# embedded-gw.net
KiCad netlist of a schematic drawn in EAGLE
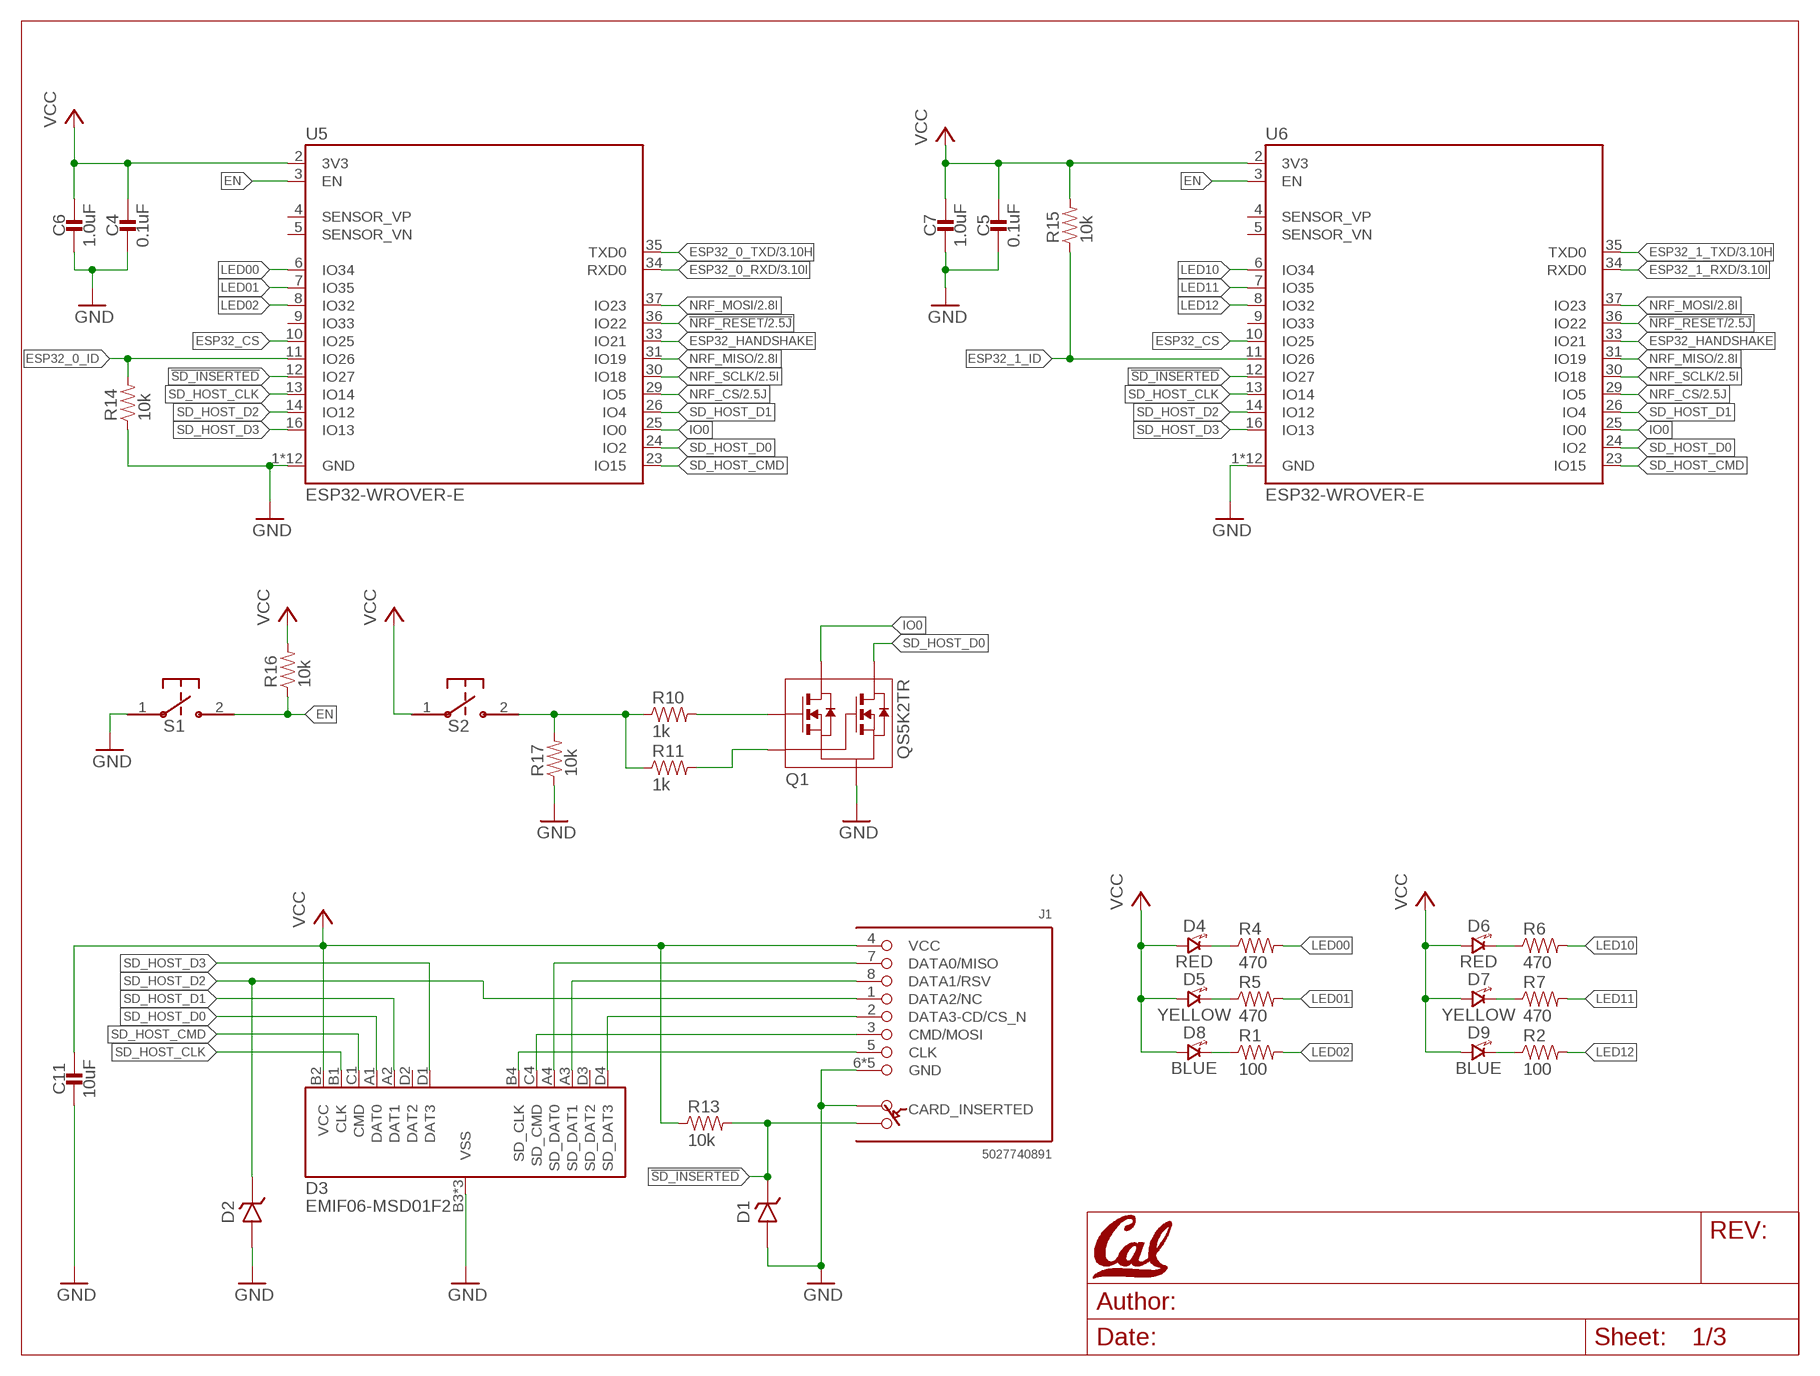
[diagram p0: schematic, sheet 1]
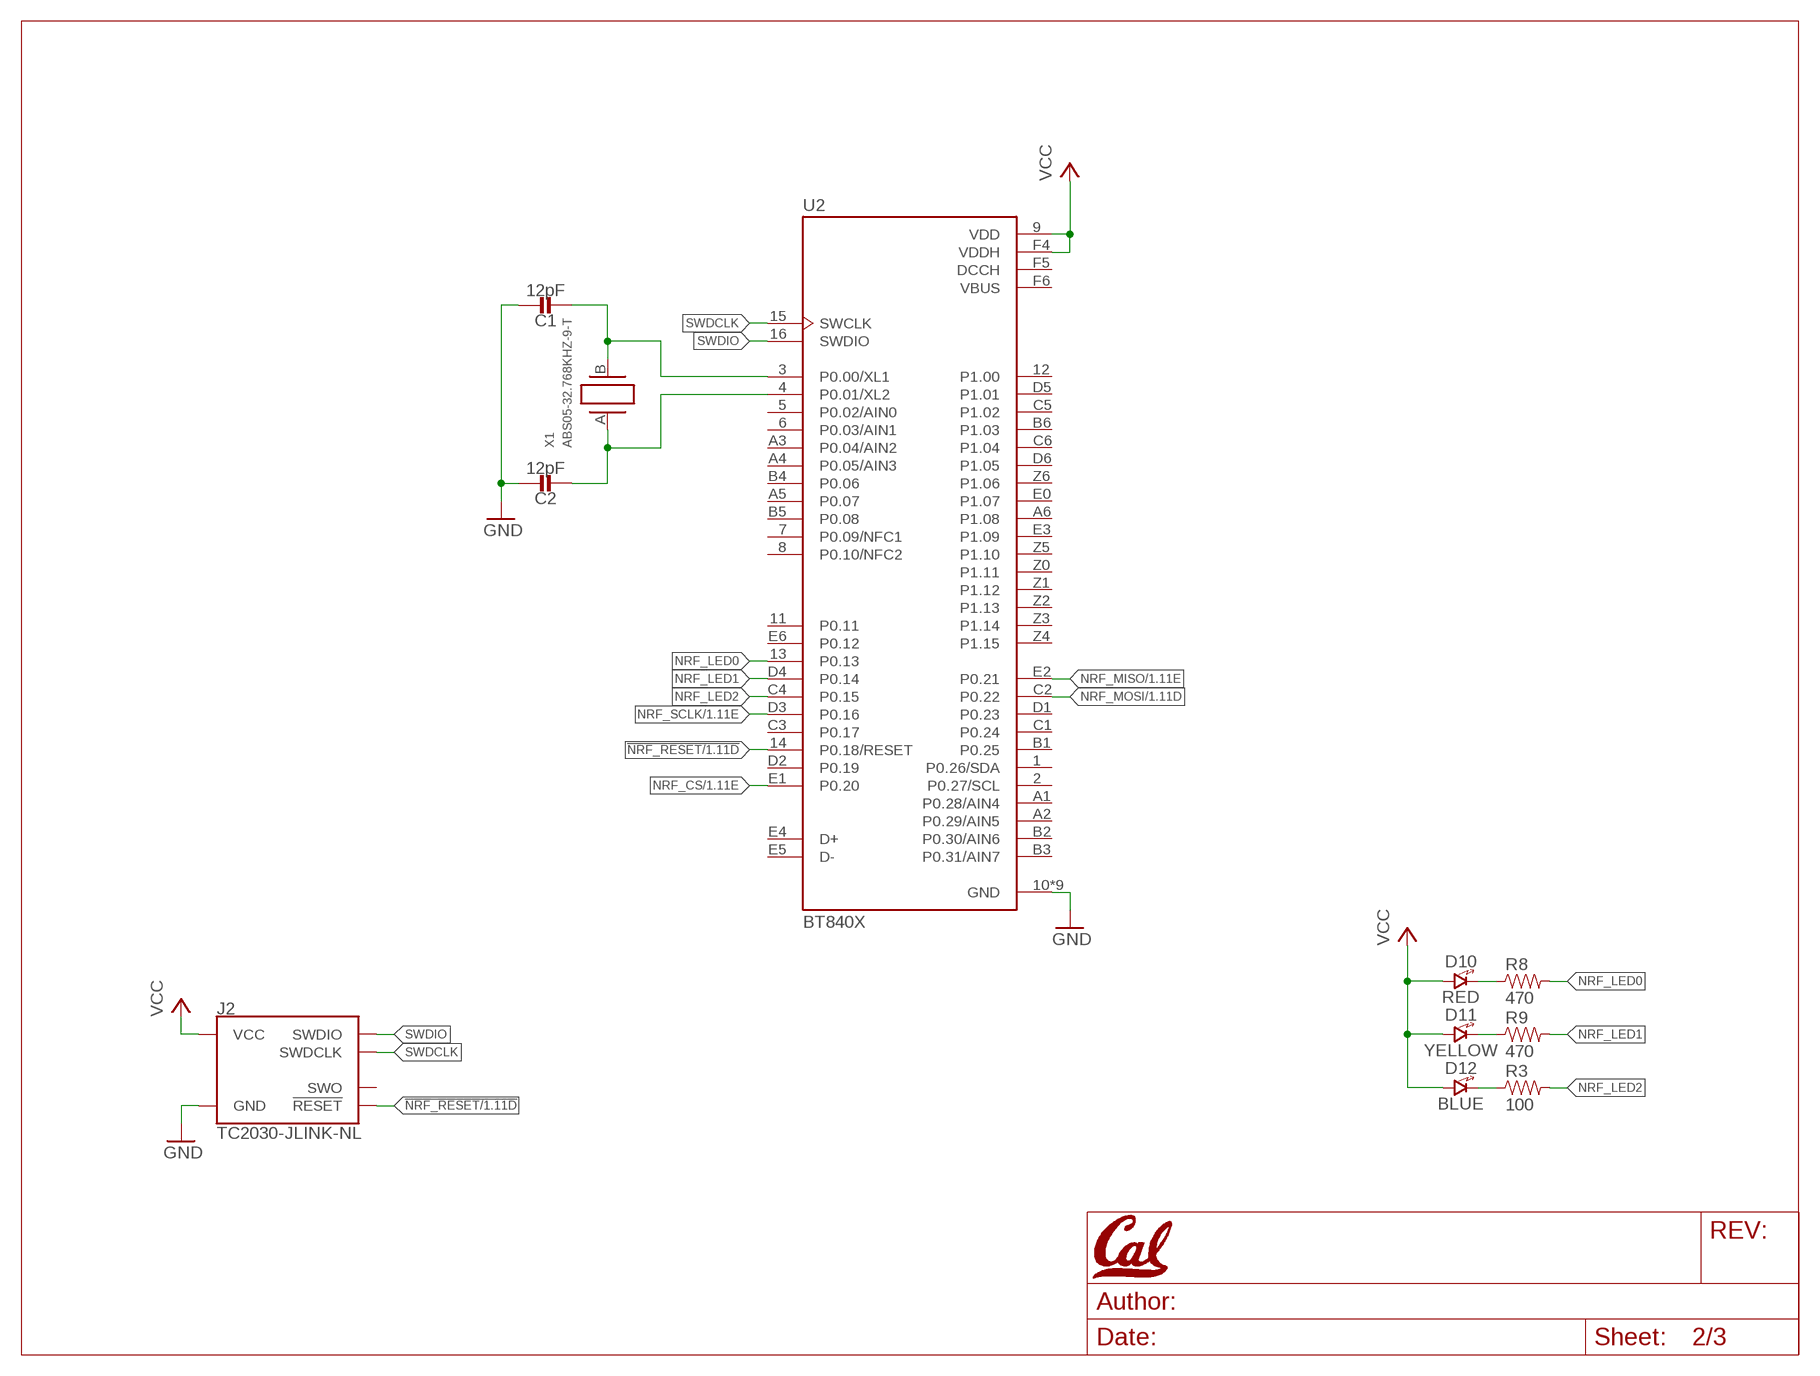
[diagram p1: schematic, sheet 2]
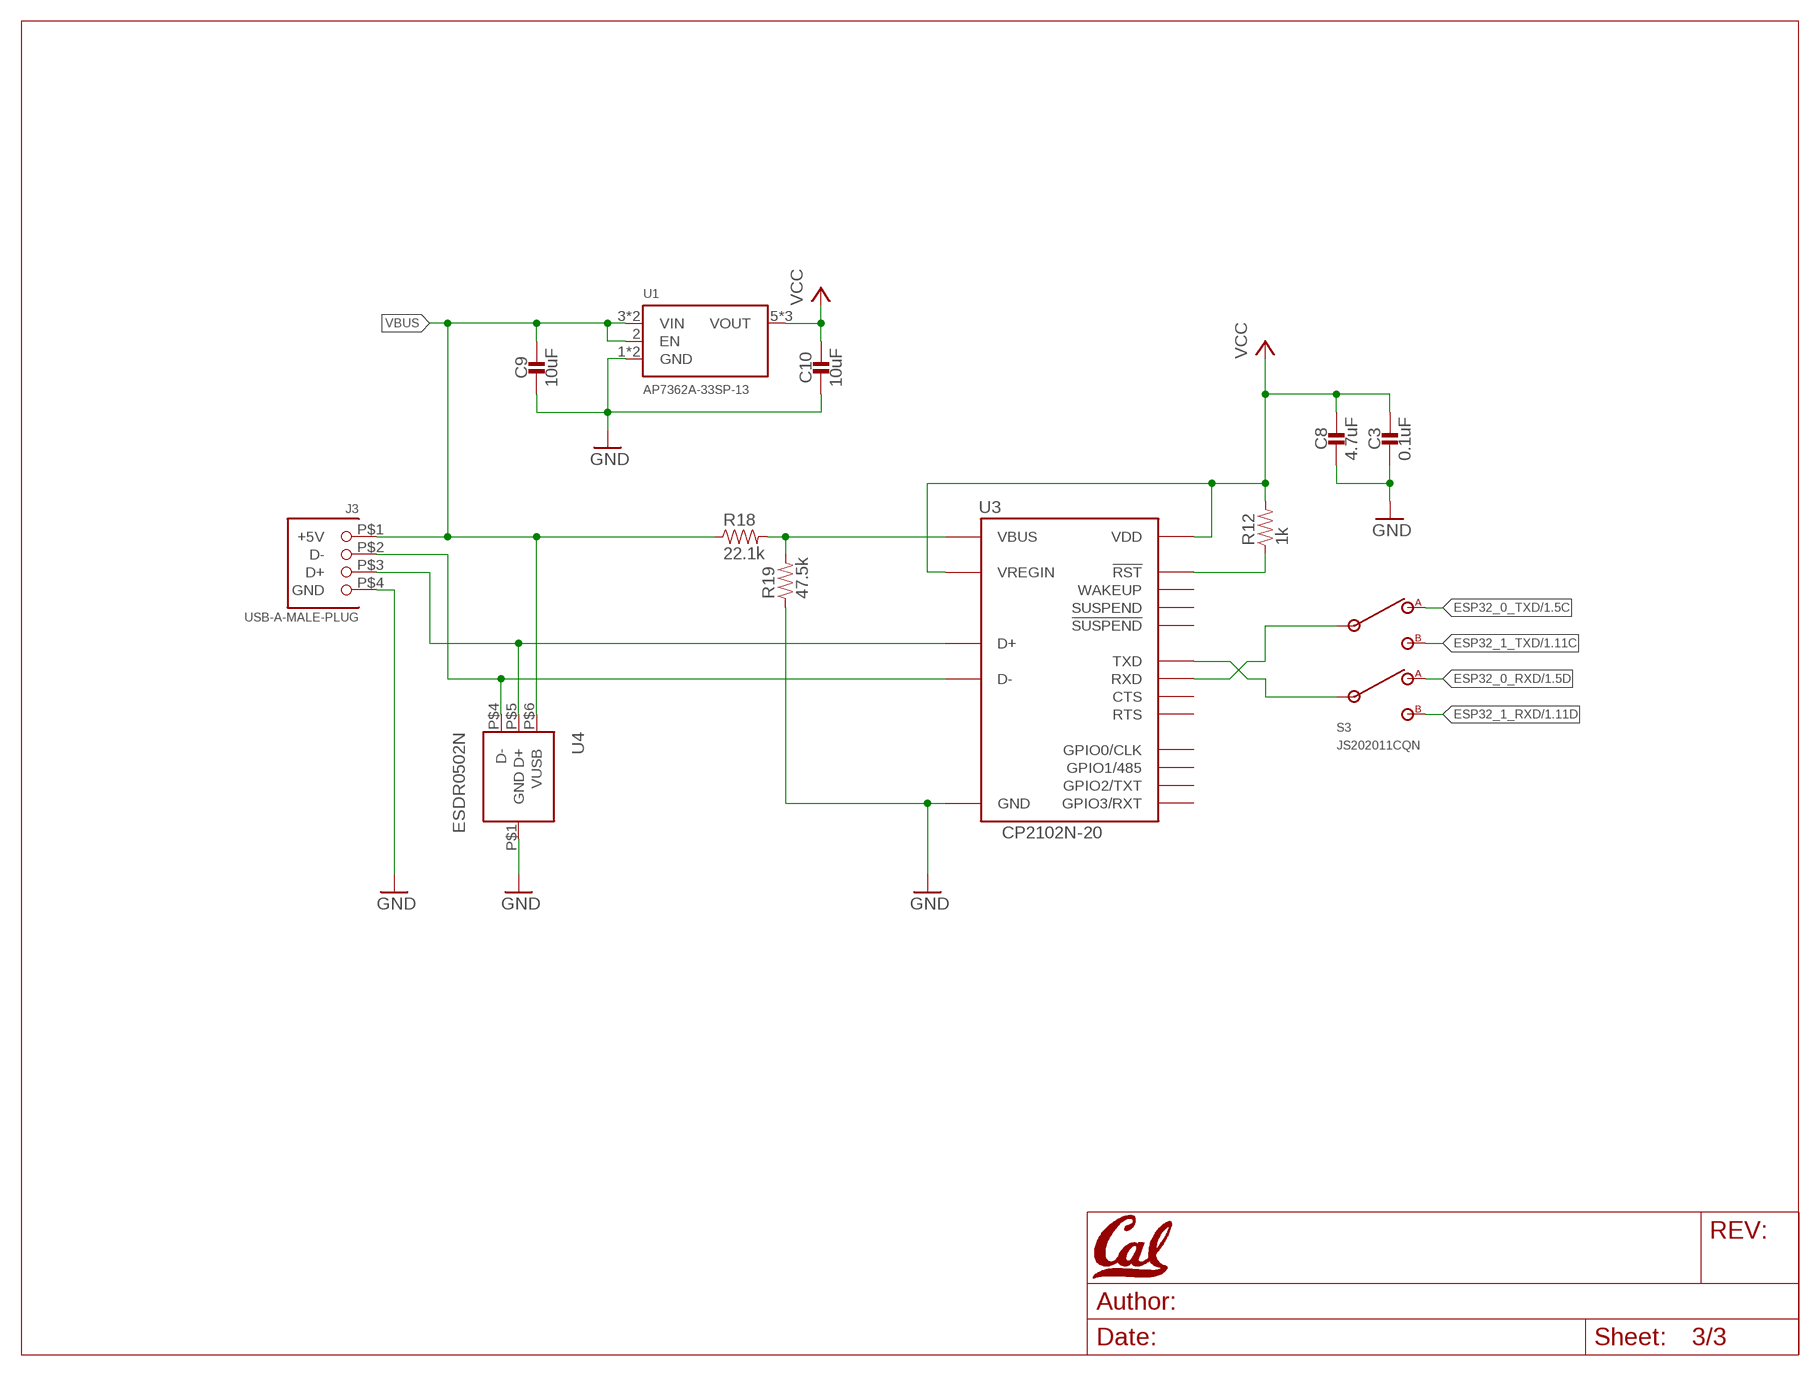
[diagram p2: schematic, sheet 3]

(export (version "E")
  (design (tool "Eeschema 10.0.6"))
  (components
    (comp (ref "C1")
      (value "12pF")
      (footprint "eagle-import:0402_CAP")
      (fields (field (name "MPN") "GCM1555C1H120GA16D"))
      (libsource (lib "eagle-import") (part "CAPACITOR0402_CAP"))
    )
    (comp (ref "C2")
      (value "12pF")
      (footprint "eagle-import:0402_CAP")
      (fields (field (name "MPN") "GCM1555C1H120GA16D"))
      (libsource (lib "eagle-import") (part "CAPACITOR0402_CAP"))
    )
    (comp (ref "D10")
      (value "RED")
      (footprint "eagle-import:LED-0603")
      (fields (field (name "MPN") "LTST-C193KRKT-5A"))
      (libsource (lib "eagle-import") (part "LED0603"))
    )
    (comp (ref "D11")
      (value "YELLOW")
      (footprint "eagle-import:LED-0603")
      (fields (field (name "MPN") "LTST-C193KSKT-5A"))
      (libsource (lib "eagle-import") (part "LED0603"))
    )
    (comp (ref "D12")
      (value "BLUE")
      (footprint "eagle-import:LED-0603")
      (fields (field (name "MPN") "LTST-C193TBKT-5A"))
      (libsource (lib "eagle-import") (part "LED0603"))
    )
    (comp (ref "J2")
      (value "TC2030-JLINK-NL")
      (footprint "eagle-import:TC2030-IDC-NL")
      (libsource (lib "eagle-import") (part "TC2030-JLINK-NL"))
    )
    (comp (ref "R3")
      (value "100")
      (footprint "eagle-import:0402_RES")
      (fields (field (name "MPN") "RC0402JR-07100RL"))
      (libsource (lib "eagle-import") (part "RESISTOR0402_RES"))
    )
    (comp (ref "R8")
      (value "470")
      (footprint "eagle-import:0402_RES")
      (fields (field (name "MPN") "RC0402FR-07470RL"))
      (libsource (lib "eagle-import") (part "RESISTOR0402_RES"))
    )
    (comp (ref "R9")
      (value "470")
      (footprint "eagle-import:0402_RES")
      (fields (field (name "MPN") "RC0402FR-07470RL"))
      (libsource (lib "eagle-import") (part "RESISTOR0402_RES"))
    )
    (comp (ref "U2")
      (value "BT840X")
      (footprint "eagle-import:XCVR_BT840X")
      (fields (field (name "MANUFACTURER") "Fanstel Corp."))
      (libsource (lib "eagle-import") (part "BT840X"))
    )
    (comp (ref "X1")
      (value "ABS05-32.768KHZ-9-T")
      (footprint "eagle-import:ABS05")
      (fields (field (name "MANUFACTURER") "Abracon"))
      (libsource (lib "eagle-import") (part "ABS05-32.768KHZ-9-T"))
    )
    (comp (ref "C4")
      (value "0.1uF")
      (footprint "eagle-import:0402_CAP")
      (fields (field (name "MPN") "CL05B104KQ5NNNC"))
      (libsource (lib "eagle-import") (part "CAPACITOR0402_CAP"))
    )
    (comp (ref "C5")
      (value "0.1uF")
      (footprint "eagle-import:0402_CAP")
      (fields (field (name "MPN") "CL05B104KQ5NNNC"))
      (libsource (lib "eagle-import") (part "CAPACITOR0402_CAP"))
    )
    (comp (ref "C6")
      (value "1.0uF")
      (footprint "eagle-import:0402_CAP")
      (fields (field (name "MPN") "CL05A105KQ5NNNC"))
      (libsource (lib "eagle-import") (part "CAPACITOR0402_CAP"))
    )
    (comp (ref "C7")
      (value "1.0uF")
      (footprint "eagle-import:0402_CAP")
      (fields (field (name "MPN") "CL05A105KQ5NNNC"))
      (libsource (lib "eagle-import") (part "CAPACITOR0402_CAP"))
    )
    (comp (ref "C11")
      (value "10uF")
      (footprint "eagle-import:0805_CAP")
      (fields (field (name "MPN") "CL21A106KQCLNNC"))
      (libsource (lib "eagle-import") (part "CAPACITOR0805_CAP"))
    )
    (comp (ref "D1")
      (value "DIODE_ZENER0201")
      (footprint "eagle-import:0201_DIODE")
      (fields (field (name "MPN") "ESD7381MUT5G"))
      (libsource (lib "eagle-import") (part "DIODE_ZENER0201"))
    )
    (comp (ref "D2")
      (value "DIODE_ZENER0201")
      (footprint "eagle-import:0201_DIODE")
      (fields (field (name "MPN") "ESD7381MUT5G"))
      (libsource (lib "eagle-import") (part "DIODE_ZENER0201"))
    )
    (comp (ref "D3")
      (value "EMIF06-MSD01F2")
      (footprint "eagle-import:BGA16C50P4X4_192X192X65N")
      (fields (field (name "MANUFACTURER") "STMicroelectronics"))
      (libsource (lib "eagle-import") (part "EMIF06-MSD01F2"))
    )
    (comp (ref "D4")
      (value "RED")
      (footprint "eagle-import:LED-0603")
      (fields (field (name "MPN") "LTST-C193KRKT-5A"))
      (libsource (lib "eagle-import") (part "LED0603"))
    )
    (comp (ref "D5")
      (value "YELLOW")
      (footprint "eagle-import:LED-0603")
      (fields (field (name "MPN") "LTST-C193KSKT-5A"))
      (libsource (lib "eagle-import") (part "LED0603"))
    )
    (comp (ref "D6")
      (value "RED")
      (footprint "eagle-import:LED-0603")
      (fields (field (name "MPN") "LTST-C193KRKT-5A"))
      (libsource (lib "eagle-import") (part "LED0603"))
    )
    (comp (ref "D7")
      (value "YELLOW")
      (footprint "eagle-import:LED-0603")
      (fields (field (name "MPN") "LTST-C193KSKT-5A"))
      (libsource (lib "eagle-import") (part "LED0603"))
    )
    (comp (ref "D8")
      (value "BLUE")
      (footprint "eagle-import:LED-0603")
      (fields (field (name "MPN") "LTST-C193TBKT-5A"))
      (libsource (lib "eagle-import") (part "LED0603"))
    )
    (comp (ref "D9")
      (value "BLUE")
      (footprint "eagle-import:LED-0603")
      (fields (field (name "MPN") "LTST-C193TBKT-5A"))
      (libsource (lib "eagle-import") (part "LED0603"))
    )
    (comp (ref "J1")
      (value "5027740891")
      (footprint "eagle-import:5027740891")
      (fields (field (name "MANUFACTURER") "Molex"))
      (libsource (lib "eagle-import") (part "5027740891"))
    )
    (comp (ref "Q1")
      (value "QS5K2TR")
      (footprint "eagle-import:SOT95P280X100-5N")
      (fields (field (name "MANUFACTURER") "Rohm"))
      (libsource (lib "eagle-import") (part "QS5K2TR"))
    )
    (comp (ref "R1")
      (value "100")
      (footprint "eagle-import:0402_RES")
      (fields (field (name "MPN") "RC0402JR-07100RL"))
      (libsource (lib "eagle-import") (part "RESISTOR0402_RES"))
    )
    (comp (ref "R2")
      (value "100")
      (footprint "eagle-import:0402_RES")
      (fields (field (name "MPN") "RC0402JR-07100RL"))
      (libsource (lib "eagle-import") (part "RESISTOR0402_RES"))
    )
    (comp (ref "R4")
      (value "470")
      (footprint "eagle-import:0402_RES")
      (fields (field (name "MPN") "RC0402FR-07470RL"))
      (libsource (lib "eagle-import") (part "RESISTOR0402_RES"))
    )
    (comp (ref "R5")
      (value "470")
      (footprint "eagle-import:0402_RES")
      (fields (field (name "MPN") "RC0402FR-07470RL"))
      (libsource (lib "eagle-import") (part "RESISTOR0402_RES"))
    )
    (comp (ref "R6")
      (value "470")
      (footprint "eagle-import:0402_RES")
      (fields (field (name "MPN") "RC0402FR-07470RL"))
      (libsource (lib "eagle-import") (part "RESISTOR0402_RES"))
    )
    (comp (ref "R7")
      (value "470")
      (footprint "eagle-import:0402_RES")
      (fields (field (name "MPN") "RC0402FR-07470RL"))
      (libsource (lib "eagle-import") (part "RESISTOR0402_RES"))
    )
    (comp (ref "R10")
      (value "1k")
      (footprint "eagle-import:0402_RES")
      (fields (field (name "MPN") "RMCF0402JT1K00"))
      (libsource (lib "eagle-import") (part "RESISTOR0402_RES"))
    )
    (comp (ref "R11")
      (value "1k")
      (footprint "eagle-import:0402_RES")
      (fields (field (name "MPN") "RMCF0402JT1K00"))
      (libsource (lib "eagle-import") (part "RESISTOR0402_RES"))
    )
    (comp (ref "R13")
      (value "10k")
      (footprint "eagle-import:0402_RES")
      (fields (field (name "MPN") "RMCF0402JT10K0"))
      (libsource (lib "eagle-import") (part "RESISTOR0402_RES"))
    )
    (comp (ref "R14")
      (value "10k")
      (footprint "eagle-import:0402_RES")
      (fields (field (name "MPN") "RMCF0402JT10K0"))
      (libsource (lib "eagle-import") (part "RESISTOR0402_RES"))
    )
    (comp (ref "R15")
      (value "10k")
      (footprint "eagle-import:0402_RES")
      (fields (field (name "MPN") "RMCF0402JT10K0"))
      (libsource (lib "eagle-import") (part "RESISTOR0402_RES"))
    )
    (comp (ref "R16")
      (value "10k")
      (footprint "eagle-import:0402_RES")
      (fields (field (name "MPN") "RMCF0402JT10K0"))
      (libsource (lib "eagle-import") (part "RESISTOR0402_RES"))
    )
    (comp (ref "R17")
      (value "10k")
      (footprint "eagle-import:0402_RES")
      (fields (field (name "MPN") "RMCF0402JT10K0"))
      (libsource (lib "eagle-import") (part "RESISTOR0402_RES"))
    )
    (comp (ref "S1")
      (value "B3U-1000P")
      (footprint "eagle-import:B3U-1000P")
      (fields (field (name "MANUFACTURER") "Omron"))
      (libsource (lib "eagle-import") (part "B3U-1000P"))
    )
    (comp (ref "S2")
      (value "B3U-1000P")
      (footprint "eagle-import:B3U-1000P")
      (fields (field (name "MANUFACTURER") "Omron"))
      (libsource (lib "eagle-import") (part "B3U-1000P"))
    )
    (comp (ref "U5")
      (value "ESP32-WROVER-E")
      (footprint "eagle-import:ESP32-WROVER-E")
      (fields (field (name "MANUFACTURER") "Espressif Systems") (field (name "MPN") "  ESP32-WROVER-E (8MB)"))
      (libsource (lib "eagle-import") (part "ESP32-WROVER-E"))
    )
    (comp (ref "U6")
      (value "ESP32-WROVER-E")
      (footprint "eagle-import:ESP32-WROVER-E")
      (fields (field (name "MANUFACTURER") "Espressif Systems") (field (name "MPN") "  ESP32-WROVER-E (8MB)"))
      (libsource (lib "eagle-import") (part "ESP32-WROVER-E"))
    )
    (comp (ref "C3")
      (value "0.1uF")
      (footprint "eagle-import:0402_CAP")
      (fields (field (name "MPN") "CL05B104KQ5NNNC"))
      (libsource (lib "eagle-import") (part "CAPACITOR0402_CAP"))
    )
    (comp (ref "C8")
      (value "4.7uF")
      (footprint "eagle-import:0603_CAP")
      (fields (field (name "MPN") "CL10A475KQ8NNNC"))
      (libsource (lib "eagle-import") (part "CAPACITOR0603_CAP"))
    )
    (comp (ref "C9")
      (value "10uF")
      (footprint "eagle-import:0805_CAP")
      (fields (field (name "MPN") "CL21A106KQCLNNC"))
      (libsource (lib "eagle-import") (part "CAPACITOR0805_CAP"))
    )
    (comp (ref "C10")
      (value "10uF")
      (footprint "eagle-import:0805_CAP")
      (fields (field (name "MPN") "CL21A106KQCLNNC"))
      (libsource (lib "eagle-import") (part "CAPACITOR0805_CAP"))
    )
    (comp (ref "J3")
      (value "USB-A-MALE-PLUG")
      (footprint "eagle-import:USB_A_MALE_PLUG_CUI_UP2-AH")
      (fields (field (name "MANUFACTURER") "CUI") (field (name "MPN") "UP2-AH-1-TH"))
      (libsource (lib "eagle-import") (part "USB-A-MALE-PLUG"))
    )
    (comp (ref "R12")
      (value "1k")
      (footprint "eagle-import:0402_RES")
      (fields (field (name "MPN") "RMCF0402JT1K00"))
      (libsource (lib "eagle-import") (part "RESISTOR0402_RES"))
    )
    (comp (ref "R18")
      (value "22.1k")
      (footprint "eagle-import:0402_RES")
      (fields (field (name "MPN") "RC0402FR-0722K1L"))
      (libsource (lib "eagle-import") (part "RESISTOR0402_RES"))
    )
    (comp (ref "R19")
      (value "47.5k")
      (footprint "eagle-import:0402_RES")
      (fields (field (name "MPN") "RT0402FRE0747K5L"))
      (libsource (lib "eagle-import") (part "RESISTOR0402_RES"))
    )
    (comp (ref "S3")
      (value "JS202011CQN")
      (footprint "eagle-import:JS202011CQN")
      (fields (field (name "MANUFACTURER") "C&K"))
      (libsource (lib "eagle-import") (part "JS202011CQN"))
    )
    (comp (ref "U1")
      (value "AP7362A-33SP-13")
      (footprint "eagle-import:SO-8EP")
      (fields (field (name "MANUFACTURER") "Diodes Incorporated") (field (name "MPN") "AP7362A-33SP-13 "))
      (libsource (lib "eagle-import") (part "AP7362A-33SP-13"))
    )
    (comp (ref "U3")
      (value "CP2102N-20")
      (footprint "eagle-import:QFN-20-3MM")
      (fields (field (name "MANUFACTURER") "SiLabs") (field (name "MPN") "CP2102N-A02-GQFN20"))
      (libsource (lib "eagle-import") (part "CP2102N-20"))
    )
    (comp (ref "U4")
      (value "ESDR0502N")
      (footprint "eagle-import:UDFN-6")
      (fields (field (name "MPN") "ESDR0502NMUTBG"))
      (libsource (lib "eagle-import") (part "ESDR0502N"))
    )
  )
  (nets
    (net (code "1") (name "DCCH") (class "Default")
      (node (ref "U2") (pin "F5") (pinfunction "DCCH_F5") (pintype "power_in"))
    )
    (net (code "2") (name "EN") (class "Default")
      (node (ref "R16") (pin "1") (pinfunction "1_1") (pintype "passive"))
      (node (ref "S1") (pin "2") (pinfunction "P$2_2") (pintype "passive"))
      (node (ref "U5") (pin "3") (pinfunction "EN_3") (pintype "bidirectional"))
      (node (ref "U6") (pin "3") (pinfunction "EN_3") (pintype "bidirectional"))
    )
    (net (code "3") (name "ESP32_0_ID") (class "Default")
      (node (ref "R14") (pin "2") (pinfunction "2_2") (pintype "passive"))
      (node (ref "U5") (pin "11") (pinfunction "IO26_11") (pintype "bidirectional"))
    )
    (net (code "4") (name "ESP32_0_RXD") (class "Default")
      (node (ref "S3") (pin "1") (pinfunction "A2_1") (pintype "bidirectional"))
      (node (ref "U5") (pin "34") (pinfunction "RXD0_34") (pintype "bidirectional"))
    )
    (net (code "5") (name "ESP32_0_TXD") (class "Default")
      (node (ref "S3") (pin "4") (pinfunction "A1_4") (pintype "bidirectional"))
      (node (ref "U5") (pin "35") (pinfunction "TXD0_35") (pintype "bidirectional"))
    )
    (net (code "6") (name "ESP32_1_ID") (class "Default")
      (node (ref "R15") (pin "1") (pinfunction "1_1") (pintype "passive"))
      (node (ref "U6") (pin "11") (pinfunction "IO26_11") (pintype "bidirectional"))
    )
    (net (code "7") (name "ESP32_1_RXD") (class "Default")
      (node (ref "S3") (pin "3") (pinfunction "B2_3") (pintype "bidirectional"))
      (node (ref "U6") (pin "34") (pinfunction "RXD0_34") (pintype "bidirectional"))
    )
    (net (code "8") (name "ESP32_1_TXD") (class "Default")
      (node (ref "S3") (pin "6") (pinfunction "B1_6") (pintype "bidirectional"))
      (node (ref "U6") (pin "35") (pinfunction "TXD0_35") (pintype "bidirectional"))
    )
    (net (code "9") (name "ESP32_CS") (class "Default")
      (node (ref "U5") (pin "10") (pinfunction "IO25_10") (pintype "bidirectional"))
      (node (ref "U6") (pin "10") (pinfunction "IO25_10") (pintype "bidirectional"))
    )
    (net (code "10") (name "ESP32_HANDSHAKE") (class "Default")
      (node (ref "U5") (pin "33") (pinfunction "IO21_33") (pintype "bidirectional"))
      (node (ref "U6") (pin "33") (pinfunction "IO21_33") (pintype "bidirectional"))
    )
    (net (code "11") (name "GND") (class "Default")
      (node (ref "C1") (pin "1") (pinfunction "1_1") (pintype "bidirectional"))
      (node (ref "C10") (pin "P$2") (pinfunction "2_P$2") (pintype "bidirectional"))
      (node (ref "C11") (pin "P$2") (pinfunction "2_P$2") (pintype "bidirectional"))
      (node (ref "C2") (pin "1") (pinfunction "1_1") (pintype "bidirectional"))
      (node (ref "C3") (pin "2") (pinfunction "2_2") (pintype "bidirectional"))
      (node (ref "C4") (pin "2") (pinfunction "2_2") (pintype "bidirectional"))
      (node (ref "C5") (pin "2") (pinfunction "2_2") (pintype "bidirectional"))
      (node (ref "C6") (pin "2") (pinfunction "2_2") (pintype "bidirectional"))
      (node (ref "C7") (pin "2") (pinfunction "2_2") (pintype "bidirectional"))
      (node (ref "C8") (pin "2") (pinfunction "2_2") (pintype "bidirectional"))
      (node (ref "C9") (pin "P$2") (pinfunction "2_P$2") (pintype "bidirectional"))
      (node (ref "D1") (pin "P$2") (pinfunction "ANODE_P$2") (pintype "bidirectional"))
      (node (ref "D2") (pin "P$2") (pinfunction "ANODE_P$2") (pintype "bidirectional"))
      (node (ref "D3") (pin "B3") (pinfunction "VSS_B3") (pintype "bidirectional"))
      (node (ref "D3") (pin "C2") (pinfunction "VSS_C2") (pintype "bidirectional"))
      (node (ref "D3") (pin "C3") (pinfunction "VSS_C3") (pintype "bidirectional"))
      (node (ref "J1") (pin "6") (pinfunction "GND_6") (pintype "bidirectional"))
      (node (ref "J1") (pin "DETECT") (pinfunction "A_DETECT") (pintype "bidirectional"))
      (node (ref "J1") (pin "GND1") (pinfunction "GND_GND1") (pintype "bidirectional"))
      (node (ref "J1") (pin "GND2") (pinfunction "GND_GND2") (pintype "bidirectional"))
      (node (ref "J1") (pin "GND3") (pinfunction "GND_GND3") (pintype "bidirectional"))
      (node (ref "J1") (pin "GND4") (pinfunction "GND_GND4") (pintype "bidirectional"))
      (node (ref "J2") (pin "5") (pinfunction "GND_5") (pintype "bidirectional"))
      (node (ref "J3") (pin "P$4") (pinfunction "GND_P$4") (pintype "bidirectional"))
      (node (ref "Q1") (pin "2") (pinfunction "S_2") (pintype "bidirectional"))
      (node (ref "R14") (pin "1") (pinfunction "1_1") (pintype "passive"))
      (node (ref "R17") (pin "1") (pinfunction "1_1") (pintype "passive"))
      (node (ref "R19") (pin "1") (pinfunction "1_1") (pintype "passive"))
      (node (ref "S1") (pin "1") (pinfunction "P$1_1") (pintype "passive"))
      (node (ref "U1") (pin "1") (pinfunction "GND_1") (pintype "bidirectional"))
      (node (ref "U1") (pin "PAD") (pinfunction "GND_PAD") (pintype "bidirectional"))
      (node (ref "U2") (pin "10") (pinfunction "GND_10") (pintype "power_in"))
      (node (ref "U2") (pin "A0") (pinfunction "GND_A0") (pintype "power_in"))
      (node (ref "U2") (pin "B0") (pinfunction "GND_B0") (pintype "power_in"))
      (node (ref "U2") (pin "C0") (pinfunction "GND_C0") (pintype "power_in"))
      (node (ref "U2") (pin "D0") (pinfunction "GND_D0") (pintype "power_in"))
      (node (ref "U2") (pin "F0") (pinfunction "GND_F0") (pintype "power_in"))
      (node (ref "U2") (pin "F1") (pinfunction "GND_F1") (pintype "power_in"))
      (node (ref "U2") (pin "F2") (pinfunction "GND_F2") (pintype "power_in"))
      (node (ref "U2") (pin "F3") (pinfunction "GND_F3") (pintype "power_in"))
      (node (ref "U3") (pin "12") (pinfunction "GND_12") (pintype "bidirectional"))
      (node (ref "U3") (pin "3") (pinfunction "GND_3") (pintype "bidirectional"))
      (node (ref "U3") (pin "P$1") (pinfunction "GND_P$1") (pintype "bidirectional"))
      (node (ref "U4") (pin "P$1") (pinfunction "GND_P$1") (pintype "bidirectional"))
      (node (ref "U5") (pin "1") (pinfunction "GND_1") (pintype "bidirectional"))
      (node (ref "U5") (pin "15") (pinfunction "GND_15") (pintype "bidirectional"))
      (node (ref "U5") (pin "38") (pinfunction "GND_38") (pintype "bidirectional"))
      (node (ref "U5") (pin "GND1") (pinfunction "GND_GND1") (pintype "bidirectional"))
      (node (ref "U5") (pin "GND2") (pinfunction "GND_GND2") (pintype "bidirectional"))
      (node (ref "U5") (pin "GND3") (pinfunction "GND_GND3") (pintype "bidirectional"))
      (node (ref "U5") (pin "GND4") (pinfunction "GND_GND4") (pintype "bidirectional"))
      (node (ref "U5") (pin "GND5") (pinfunction "GND_GND5") (pintype "bidirectional"))
      (node (ref "U5") (pin "GND6") (pinfunction "GND_GND6") (pintype "bidirectional"))
      (node (ref "U5") (pin "GND7") (pinfunction "GND_GND7") (pintype "bidirectional"))
      (node (ref "U5") (pin "GND8") (pinfunction "GND_GND8") (pintype "bidirectional"))
      (node (ref "U5") (pin "GND9") (pinfunction "GND_GND9") (pintype "bidirectional"))
      (node (ref "U6") (pin "1") (pinfunction "GND_1") (pintype "bidirectional"))
      (node (ref "U6") (pin "15") (pinfunction "GND_15") (pintype "bidirectional"))
      (node (ref "U6") (pin "38") (pinfunction "GND_38") (pintype "bidirectional"))
      (node (ref "U6") (pin "GND1") (pinfunction "GND_GND1") (pintype "bidirectional"))
      (node (ref "U6") (pin "GND2") (pinfunction "GND_GND2") (pintype "bidirectional"))
      (node (ref "U6") (pin "GND3") (pinfunction "GND_GND3") (pintype "bidirectional"))
      (node (ref "U6") (pin "GND4") (pinfunction "GND_GND4") (pintype "bidirectional"))
      (node (ref "U6") (pin "GND5") (pinfunction "GND_GND5") (pintype "bidirectional"))
      (node (ref "U6") (pin "GND6") (pinfunction "GND_GND6") (pintype "bidirectional"))
      (node (ref "U6") (pin "GND7") (pinfunction "GND_GND7") (pintype "bidirectional"))
      (node (ref "U6") (pin "GND8") (pinfunction "GND_GND8") (pintype "bidirectional"))
      (node (ref "U6") (pin "GND9") (pinfunction "GND_GND9") (pintype "bidirectional"))
    )
    (net (code "12") (name "IO0") (class "Default")
      (node (ref "Q1") (pin "5") (pinfunction "D1_5") (pintype "bidirectional"))
      (node (ref "U5") (pin "25") (pinfunction "IO0_25") (pintype "bidirectional"))
      (node (ref "U6") (pin "25") (pinfunction "IO0_25") (pintype "bidirectional"))
    )
    (net (code "13") (name "LED00") (class "Default")
      (node (ref "R4") (pin "2") (pinfunction "2_2") (pintype "passive"))
      (node (ref "U5") (pin "6") (pinfunction "IO34_6") (pintype "bidirectional"))
    )
    (net (code "14") (name "LED01") (class "Default")
      (node (ref "R5") (pin "2") (pinfunction "2_2") (pintype "passive"))
      (node (ref "U5") (pin "7") (pinfunction "IO35_7") (pintype "bidirectional"))
    )
    (net (code "15") (name "LED02") (class "Default")
      (node (ref "R1") (pin "2") (pinfunction "2_2") (pintype "passive"))
      (node (ref "U5") (pin "8") (pinfunction "IO32_8") (pintype "bidirectional"))
    )
    (net (code "16") (name "LED10") (class "Default")
      (node (ref "R6") (pin "2") (pinfunction "2_2") (pintype "passive"))
      (node (ref "U6") (pin "6") (pinfunction "IO34_6") (pintype "bidirectional"))
    )
    (net (code "17") (name "LED11") (class "Default")
      (node (ref "R7") (pin "2") (pinfunction "2_2") (pintype "passive"))
      (node (ref "U6") (pin "7") (pinfunction "IO35_7") (pintype "bidirectional"))
    )
    (net (code "18") (name "LED12") (class "Default")
      (node (ref "R2") (pin "2") (pinfunction "2_2") (pintype "passive"))
      (node (ref "U6") (pin "8") (pinfunction "IO32_8") (pintype "bidirectional"))
    )
    (net (code "19") (name "NRF_CS") (class "Default")
      (node (ref "U2") (pin "E1") (pinfunction "P0.20_E1") (pintype "bidirectional"))
      (node (ref "U5") (pin "29") (pinfunction "IO5_29") (pintype "bidirectional"))
      (node (ref "U6") (pin "29") (pinfunction "IO5_29") (pintype "bidirectional"))
    )
    (net (code "20") (name "NRF_LED0") (class "Default")
      (node (ref "R8") (pin "2") (pinfunction "2_2") (pintype "passive"))
      (node (ref "U2") (pin "13") (pinfunction "P0.13_13") (pintype "bidirectional"))
    )
    (net (code "21") (name "NRF_LED1") (class "Default")
      (node (ref "R9") (pin "2") (pinfunction "2_2") (pintype "passive"))
      (node (ref "U2") (pin "D4") (pinfunction "P0.14_D4") (pintype "bidirectional"))
    )
    (net (code "22") (name "NRF_LED2") (class "Default")
      (node (ref "R3") (pin "2") (pinfunction "2_2") (pintype "passive"))
      (node (ref "U2") (pin "C4") (pinfunction "P0.15_C4") (pintype "bidirectional"))
    )
    (net (code "23") (name "NRF_MISO") (class "Default")
      (node (ref "U2") (pin "E2") (pinfunction "P0.21_E2") (pintype "bidirectional"))
      (node (ref "U5") (pin "31") (pinfunction "IO19_31") (pintype "bidirectional"))
      (node (ref "U6") (pin "31") (pinfunction "IO19_31") (pintype "bidirectional"))
    )
    (net (code "24") (name "NRF_MOSI") (class "Default")
      (node (ref "U2") (pin "C2") (pinfunction "P0.22_C2") (pintype "bidirectional"))
      (node (ref "U5") (pin "37") (pinfunction "IO23_37") (pintype "bidirectional"))
      (node (ref "U6") (pin "37") (pinfunction "IO23_37") (pintype "bidirectional"))
    )
    (net (code "25") (name "NRF_SCLK") (class "Default")
      (node (ref "U2") (pin "D3") (pinfunction "P0.16_D3") (pintype "bidirectional"))
      (node (ref "U5") (pin "30") (pinfunction "IO18_30") (pintype "bidirectional"))
      (node (ref "U6") (pin "30") (pinfunction "IO18_30") (pintype "bidirectional"))
    )
    (net (code "26") (name "Net-(D3-SD_CLK)") (class "Default")
      (node (ref "D3") (pin "B4") (pinfunction "SD_CLK_B4") (pintype "bidirectional"))
      (node (ref "J1") (pin "5") (pinfunction "CLK_5") (pintype "bidirectional"))
    )
    (net (code "27") (name "Net-(D3-SD_CMD)") (class "Default")
      (node (ref "D3") (pin "C4") (pinfunction "SD_CMD_C4") (pintype "bidirectional"))
      (node (ref "J1") (pin "3") (pinfunction "CMD/MOSI_3") (pintype "bidirectional"))
    )
    (net (code "28") (name "Net-(D3-SD_DAT0)") (class "Default")
      (node (ref "D3") (pin "A4") (pinfunction "SD_DAT0_A4") (pintype "bidirectional"))
      (node (ref "J1") (pin "7") (pinfunction "DATA0/MISO_7") (pintype "bidirectional"))
    )
    (net (code "29") (name "Net-(D3-SD_DAT1)") (class "Default")
      (node (ref "D3") (pin "A3") (pinfunction "SD_DAT1_A3") (pintype "bidirectional"))
      (node (ref "J1") (pin "8") (pinfunction "DATA1/RSV_8") (pintype "bidirectional"))
    )
    (net (code "30") (name "Net-(D3-SD_DAT3)") (class "Default")
      (node (ref "D3") (pin "D4") (pinfunction "SD_DAT3_D4") (pintype "bidirectional"))
      (node (ref "J1") (pin "2") (pinfunction "DATA3-CD/CS_N_2") (pintype "bidirectional"))
    )
    (net (code "31") (name "Net-(D4-CATHODE)") (class "Default")
      (node (ref "D4") (pin "C") (pinfunction "CATHODE_C") (pintype "bidirectional"))
      (node (ref "R4") (pin "1") (pinfunction "1_1") (pintype "passive"))
    )
    (net (code "32") (name "Net-(D5-CATHODE)") (class "Default")
      (node (ref "D5") (pin "C") (pinfunction "CATHODE_C") (pintype "bidirectional"))
      (node (ref "R5") (pin "1") (pinfunction "1_1") (pintype "passive"))
    )
    (net (code "33") (name "Net-(D6-CATHODE)") (class "Default")
      (node (ref "D6") (pin "C") (pinfunction "CATHODE_C") (pintype "bidirectional"))
      (node (ref "R6") (pin "1") (pinfunction "1_1") (pintype "passive"))
    )
    (net (code "34") (name "Net-(D7-CATHODE)") (class "Default")
      (node (ref "D7") (pin "C") (pinfunction "CATHODE_C") (pintype "bidirectional"))
      (node (ref "R7") (pin "1") (pinfunction "1_1") (pintype "passive"))
    )
    (net (code "35") (name "Net-(D8-CATHODE)") (class "Default")
      (node (ref "D8") (pin "C") (pinfunction "CATHODE_C") (pintype "bidirectional"))
      (node (ref "R1") (pin "1") (pinfunction "1_1") (pintype "passive"))
    )
    (net (code "36") (name "Net-(D9-CATHODE)") (class "Default")
      (node (ref "D9") (pin "C") (pinfunction "CATHODE_C") (pintype "bidirectional"))
      (node (ref "R2") (pin "1") (pinfunction "1_1") (pintype "passive"))
    )
    (net (code "37") (name "Net-(D10-CATHODE)") (class "Default")
      (node (ref "D10") (pin "C") (pinfunction "CATHODE_C") (pintype "bidirectional"))
      (node (ref "R8") (pin "1") (pinfunction "1_1") (pintype "passive"))
    )
    (net (code "38") (name "Net-(D11-CATHODE)") (class "Default")
      (node (ref "D11") (pin "C") (pinfunction "CATHODE_C") (pintype "bidirectional"))
      (node (ref "R9") (pin "1") (pinfunction "1_1") (pintype "passive"))
    )
    (net (code "39") (name "Net-(D12-CATHODE)") (class "Default")
      (node (ref "D12") (pin "C") (pinfunction "CATHODE_C") (pintype "bidirectional"))
      (node (ref "R3") (pin "1") (pinfunction "1_1") (pintype "passive"))
    )
    (net (code "40") (name "Net-(J3-D+)") (class "Default")
      (node (ref "J3") (pin "P$3") (pinfunction "D+_P$3") (pintype "bidirectional"))
      (node (ref "U3") (pin "4") (pinfunction "D+_4") (pintype "bidirectional"))
      (node (ref "U4") (pin "P$5") (pinfunction "D+_P$5") (pintype "bidirectional"))
    )
    (net (code "41") (name "Net-(J3-D-)") (class "Default")
      (node (ref "J3") (pin "P$2") (pinfunction "D-_P$2") (pintype "bidirectional"))
      (node (ref "U3") (pin "5") (pinfunction "D-_5") (pintype "bidirectional"))
      (node (ref "U4") (pin "P$4") (pinfunction "D-_P$4") (pintype "bidirectional"))
    )
    (net (code "42") (name "Net-(Q1-G1)") (class "Default")
      (node (ref "Q1") (pin "1") (pinfunction "G1_1") (pintype "input"))
      (node (ref "R10") (pin "2") (pinfunction "2_2") (pintype "passive"))
    )
    (net (code "43") (name "Net-(Q1-G2)") (class "Default")
      (node (ref "Q1") (pin "3") (pinfunction "G2_3") (pintype "input"))
      (node (ref "R11") (pin "2") (pinfunction "2_2") (pintype "passive"))
    )
    (net (code "44") (name "Net-(S2-P$2)") (class "Default")
      (node (ref "R10") (pin "1") (pinfunction "1_1") (pintype "passive"))
      (node (ref "R11") (pin "1") (pinfunction "1_1") (pintype "passive"))
      (node (ref "R17") (pin "2") (pinfunction "2_2") (pintype "passive"))
      (node (ref "S2") (pin "2") (pinfunction "P$2_2") (pintype "passive"))
    )
    (net (code "45") (name "Net-(S3-I1)") (class "Default")
      (node (ref "S3") (pin "5") (pinfunction "I1_5") (pintype "bidirectional"))
      (node (ref "U3") (pin "17") (pinfunction "RXD_17") (pintype "bidirectional"))
    )
    (net (code "46") (name "Net-(S3-I2)") (class "Default")
      (node (ref "S3") (pin "2") (pinfunction "I2_2") (pintype "bidirectional"))
      (node (ref "U3") (pin "18") (pinfunction "TXD_18") (pintype "bidirectional"))
    )
    (net (code "47") (name "Net-(U2-P0.00{slash}XL1)") (class "Default")
      (node (ref "C1") (pin "2") (pinfunction "2_2") (pintype "bidirectional"))
      (node (ref "U2") (pin "3") (pinfunction "P0.00/XL1_3") (pintype "bidirectional"))
      (node (ref "X1") (pin "B") (pinfunction "2_B") (pintype "bidirectional"))
    )
    (net (code "48") (name "Net-(U2-P0.01{slash}XL2)") (class "Default")
      (node (ref "C2") (pin "2") (pinfunction "2_2") (pintype "bidirectional"))
      (node (ref "U2") (pin "4") (pinfunction "P0.01/XL2_4") (pintype "bidirectional"))
      (node (ref "X1") (pin "A") (pinfunction "1_A") (pintype "bidirectional"))
    )
    (net (code "49") (name "Net-(U3-VBUS)") (class "Default")
      (node (ref "R18") (pin "2") (pinfunction "2_2") (pintype "passive"))
      (node (ref "R19") (pin "2") (pinfunction "2_2") (pintype "passive"))
      (node (ref "U3") (pin "8") (pinfunction "VBUS_8") (pintype "bidirectional"))
    )
    (net (code "50") (name "Net-(U3-~{RST})") (class "Default")
      (node (ref "R12") (pin "1") (pinfunction "1_1") (pintype "passive"))
      (node (ref "U3") (pin "9") (pinfunction "~{RST}_9") (pintype "bidirectional"))
    )
    (net (code "51") (name "SD_HOST_CLK") (class "Default")
      (node (ref "D3") (pin "B1") (pinfunction "CLK_B1") (pintype "bidirectional"))
      (node (ref "U5") (pin "13") (pinfunction "IO14_13") (pintype "bidirectional"))
      (node (ref "U6") (pin "13") (pinfunction "IO14_13") (pintype "bidirectional"))
    )
    (net (code "52") (name "SD_HOST_CMD") (class "Default")
      (node (ref "D3") (pin "C1") (pinfunction "CMD_C1") (pintype "bidirectional"))
      (node (ref "U5") (pin "23") (pinfunction "IO15_23") (pintype "bidirectional"))
      (node (ref "U6") (pin "23") (pinfunction "IO15_23") (pintype "bidirectional"))
    )
    (net (code "53") (name "SD_HOST_D0") (class "Default")
      (node (ref "D3") (pin "A1") (pinfunction "DAT0_A1") (pintype "bidirectional"))
      (node (ref "Q1") (pin "4") (pinfunction "D2_4") (pintype "bidirectional"))
      (node (ref "U5") (pin "24") (pinfunction "IO2_24") (pintype "bidirectional"))
      (node (ref "U6") (pin "24") (pinfunction "IO2_24") (pintype "bidirectional"))
    )
    (net (code "54") (name "SD_HOST_D1") (class "Default")
      (node (ref "D3") (pin "A2") (pinfunction "DAT1_A2") (pintype "bidirectional"))
      (node (ref "U5") (pin "26") (pinfunction "IO4_26") (pintype "bidirectional"))
      (node (ref "U6") (pin "26") (pinfunction "IO4_26") (pintype "bidirectional"))
    )
    (net (code "55") (name "SD_HOST_D2") (class "Default")
      (node (ref "D2") (pin "P$1") (pinfunction "CATHODE_P$1") (pintype "bidirectional"))
      (node (ref "J1") (pin "1") (pinfunction "DATA2/NC_1") (pintype "bidirectional"))
      (node (ref "U5") (pin "14") (pinfunction "IO12_14") (pintype "bidirectional"))
      (node (ref "U6") (pin "14") (pinfunction "IO12_14") (pintype "bidirectional"))
    )
    (net (code "56") (name "SD_HOST_D3") (class "Default")
      (node (ref "D3") (pin "D1") (pinfunction "DAT3_D1") (pintype "bidirectional"))
      (node (ref "U5") (pin "16") (pinfunction "IO13_16") (pintype "bidirectional"))
      (node (ref "U6") (pin "16") (pinfunction "IO13_16") (pintype "bidirectional"))
    )
    (net (code "57") (name "SWDCLK") (class "Default")
      (node (ref "J2") (pin "4") (pinfunction "SWDCLK_4") (pintype "bidirectional"))
      (node (ref "U2") (pin "15") (pinfunction "SWCLK_15") (pintype "input"))
    )
    (net (code "58") (name "SWDIO") (class "Default")
      (node (ref "J2") (pin "2") (pinfunction "SWDIO_2") (pintype "bidirectional"))
      (node (ref "U2") (pin "16") (pinfunction "SWDIO_16") (pintype "bidirectional"))
    )
    (net (code "59") (name "VBUS") (class "Default")
      (node (ref "C9") (pin "P$1") (pinfunction "1_P$1") (pintype "bidirectional"))
      (node (ref "J3") (pin "P$1") (pinfunction "+5V_P$1") (pintype "bidirectional"))
      (node (ref "R18") (pin "1") (pinfunction "1_1") (pintype "passive"))
      (node (ref "U1") (pin "2") (pinfunction "EN_2") (pintype "bidirectional"))
      (node (ref "U1") (pin "3") (pinfunction "VIN_3") (pintype "bidirectional"))
      (node (ref "U1") (pin "4") (pinfunction "VIN_4") (pintype "bidirectional"))
      (node (ref "U4") (pin "P$6") (pinfunction "VUSB_P$6") (pintype "bidirectional"))
    )
    (net (code "60") (name "VCC") (class "Default")
      (node (ref "C10") (pin "P$1") (pinfunction "1_P$1") (pintype "bidirectional"))
      (node (ref "C11") (pin "P$1") (pinfunction "1_P$1") (pintype "bidirectional"))
      (node (ref "C3") (pin "1") (pinfunction "1_1") (pintype "bidirectional"))
      (node (ref "C4") (pin "1") (pinfunction "1_1") (pintype "bidirectional"))
      (node (ref "C5") (pin "1") (pinfunction "1_1") (pintype "bidirectional"))
      (node (ref "C6") (pin "1") (pinfunction "1_1") (pintype "bidirectional"))
      (node (ref "C7") (pin "1") (pinfunction "1_1") (pintype "bidirectional"))
      (node (ref "C8") (pin "1") (pinfunction "1_1") (pintype "bidirectional"))
      (node (ref "D10") (pin "A") (pinfunction "ANODE_A") (pintype "bidirectional"))
      (node (ref "D11") (pin "A") (pinfunction "ANODE_A") (pintype "bidirectional"))
      (node (ref "D12") (pin "A") (pinfunction "ANODE_A") (pintype "bidirectional"))
      (node (ref "D3") (pin "B2") (pinfunction "VCC_B2") (pintype "bidirectional"))
      (node (ref "D4") (pin "A") (pinfunction "ANODE_A") (pintype "bidirectional"))
      (node (ref "D5") (pin "A") (pinfunction "ANODE_A") (pintype "bidirectional"))
      (node (ref "D6") (pin "A") (pinfunction "ANODE_A") (pintype "bidirectional"))
      (node (ref "D7") (pin "A") (pinfunction "ANODE_A") (pintype "bidirectional"))
      (node (ref "D8") (pin "A") (pinfunction "ANODE_A") (pintype "bidirectional"))
      (node (ref "D9") (pin "A") (pinfunction "ANODE_A") (pintype "bidirectional"))
      (node (ref "J1") (pin "4") (pinfunction "VCC_4") (pintype "bidirectional"))
      (node (ref "J2") (pin "1") (pinfunction "VCC_1") (pintype "bidirectional"))
      (node (ref "R12") (pin "2") (pinfunction "2_2") (pintype "passive"))
      (node (ref "R13") (pin "1") (pinfunction "1_1") (pintype "passive"))
      (node (ref "R15") (pin "2") (pinfunction "2_2") (pintype "passive"))
      (node (ref "R16") (pin "2") (pinfunction "2_2") (pintype "passive"))
      (node (ref "S2") (pin "1") (pinfunction "P$1_1") (pintype "passive"))
      (node (ref "U1") (pin "5") (pinfunction "VOUT_5") (pintype "bidirectional"))
      (node (ref "U1") (pin "6") (pinfunction "VOUT_6") (pintype "bidirectional"))
      (node (ref "U1") (pin "7") (pinfunction "VOUT_7") (pintype "bidirectional"))
      (node (ref "U2") (pin "9") (pinfunction "VDD_9") (pintype "power_in"))
      (node (ref "U2") (pin "F4") (pinfunction "VDDH_F4") (pintype "power_in"))
      (node (ref "U3") (pin "6") (pinfunction "VDD_6") (pintype "bidirectional"))
      (node (ref "U3") (pin "7") (pinfunction "VREGIN_7") (pintype "bidirectional"))
      (node (ref "U5") (pin "2") (pinfunction "3V3_2") (pintype "bidirectional"))
      (node (ref "U6") (pin "2") (pinfunction "3V3_2") (pintype "bidirectional"))
    )
    (net (code "61") (name "unconnected-(D3-DAT2-PadD2)") (class "Default")
      (node (ref "D3") (pin "D2") (pinfunction "DAT2_D2") (pintype "bidirectional"))
    )
    (net (code "62") (name "unconnected-(D3-SD_DAT2-PadD3)") (class "Default")
      (node (ref "D3") (pin "D3") (pinfunction "SD_DAT2_D3") (pintype "bidirectional"))
    )
    (net (code "63") (name "unconnected-(J2-SWO-Pad6)") (class "Default")
      (node (ref "J2") (pin "6") (pinfunction "SWO_6") (pintype "bidirectional"))
    )
    (net (code "64") (name "unconnected-(U2-D+-PadE4)") (class "Default")
      (node (ref "U2") (pin "E4") (pinfunction "D+_E4") (pintype "bidirectional"))
    )
    (net (code "65") (name "unconnected-(U2-D--PadE5)") (class "Default")
      (node (ref "U2") (pin "E5") (pinfunction "D-_E5") (pintype "bidirectional"))
    )
    (net (code "66") (name "unconnected-(U2-P0.02{slash}AIN0-Pad5)") (class "Default")
      (node (ref "U2") (pin "5") (pinfunction "P0.02/AIN0_5") (pintype "bidirectional"))
    )
    (net (code "67") (name "unconnected-(U2-P0.03{slash}AIN1-Pad6)") (class "Default")
      (node (ref "U2") (pin "6") (pinfunction "P0.03/AIN1_6") (pintype "bidirectional"))
    )
    (net (code "68") (name "unconnected-(U2-P0.04{slash}AIN2-PadA3)") (class "Default")
      (node (ref "U2") (pin "A3") (pinfunction "P0.04/AIN2_A3") (pintype "bidirectional"))
    )
    (net (code "69") (name "unconnected-(U2-P0.05{slash}AIN3-PadA4)") (class "Default")
      (node (ref "U2") (pin "A4") (pinfunction "P0.05/AIN3_A4") (pintype "bidirectional"))
    )
    (net (code "70") (name "unconnected-(U2-P0.06-PadB4)") (class "Default")
      (node (ref "U2") (pin "B4") (pinfunction "P0.06_B4") (pintype "bidirectional"))
    )
    (net (code "71") (name "unconnected-(U2-P0.07-PadA5)") (class "Default")
      (node (ref "U2") (pin "A5") (pinfunction "P0.07_A5") (pintype "bidirectional"))
    )
    (net (code "72") (name "unconnected-(U2-P0.08-PadB5)") (class "Default")
      (node (ref "U2") (pin "B5") (pinfunction "P0.08_B5") (pintype "bidirectional"))
    )
    (net (code "73") (name "unconnected-(U2-P0.09{slash}NFC1-Pad7)") (class "Default")
      (node (ref "U2") (pin "7") (pinfunction "P0.09/NFC1_7") (pintype "bidirectional"))
    )
    (net (code "74") (name "unconnected-(U2-P0.10{slash}NFC2-Pad8)") (class "Default")
      (node (ref "U2") (pin "8") (pinfunction "P0.10/NFC2_8") (pintype "bidirectional"))
    )
    (net (code "75") (name "unconnected-(U2-P0.11-Pad11)") (class "Default")
      (node (ref "U2") (pin "11") (pinfunction "P0.11_11") (pintype "bidirectional"))
    )
    (net (code "76") (name "unconnected-(U2-P0.12-PadE6)") (class "Default")
      (node (ref "U2") (pin "E6") (pinfunction "P0.12_E6") (pintype "bidirectional"))
    )
    (net (code "77") (name "unconnected-(U2-P0.17-PadC3)") (class "Default")
      (node (ref "U2") (pin "C3") (pinfunction "P0.17_C3") (pintype "bidirectional"))
    )
    (net (code "78") (name "unconnected-(U2-P0.19-PadD2)") (class "Default")
      (node (ref "U2") (pin "D2") (pinfunction "P0.19_D2") (pintype "bidirectional"))
    )
    (net (code "79") (name "unconnected-(U2-P0.23-PadD1)") (class "Default")
      (node (ref "U2") (pin "D1") (pinfunction "P0.23_D1") (pintype "bidirectional"))
    )
    (net (code "80") (name "unconnected-(U2-P0.24-PadC1)") (class "Default")
      (node (ref "U2") (pin "C1") (pinfunction "P0.24_C1") (pintype "bidirectional"))
    )
    (net (code "81") (name "unconnected-(U2-P0.25-PadB1)") (class "Default")
      (node (ref "U2") (pin "B1") (pinfunction "P0.25_B1") (pintype "bidirectional"))
    )
    (net (code "82") (name "unconnected-(U2-P0.26{slash}SDA-Pad1)") (class "Default")
      (node (ref "U2") (pin "1") (pinfunction "P0.26/SDA_1") (pintype "bidirectional"))
    )
    (net (code "83") (name "unconnected-(U2-P0.27{slash}SCL-Pad2)") (class "Default")
      (node (ref "U2") (pin "2") (pinfunction "P0.27/SCL_2") (pintype "bidirectional"))
    )
    (net (code "84") (name "unconnected-(U2-P0.28{slash}AIN4-PadA1)") (class "Default")
      (node (ref "U2") (pin "A1") (pinfunction "P0.28/AIN4_A1") (pintype "bidirectional"))
    )
    (net (code "85") (name "unconnected-(U2-P0.29{slash}AIN5-PadA2)") (class "Default")
      (node (ref "U2") (pin "A2") (pinfunction "P0.29/AIN5_A2") (pintype "bidirectional"))
    )
    (net (code "86") (name "unconnected-(U2-P0.30{slash}AIN6-PadB2)") (class "Default")
      (node (ref "U2") (pin "B2") (pinfunction "P0.30/AIN6_B2") (pintype "bidirectional"))
    )
    (net (code "87") (name "unconnected-(U2-P0.31{slash}AIN7-PadB3)") (class "Default")
      (node (ref "U2") (pin "B3") (pinfunction "P0.31/AIN7_B3") (pintype "bidirectional"))
    )
    (net (code "88") (name "unconnected-(U2-P1.00-Pad12)") (class "Default")
      (node (ref "U2") (pin "12") (pinfunction "P1.00_12") (pintype "bidirectional"))
    )
    (net (code "89") (name "unconnected-(U2-P1.01-PadD5)") (class "Default")
      (node (ref "U2") (pin "D5") (pinfunction "P1.01_D5") (pintype "bidirectional"))
    )
    (net (code "90") (name "unconnected-(U2-P1.02-PadC5)") (class "Default")
      (node (ref "U2") (pin "C5") (pinfunction "P1.02_C5") (pintype "bidirectional"))
    )
    (net (code "91") (name "unconnected-(U2-P1.03-PadB6)") (class "Default")
      (node (ref "U2") (pin "B6") (pinfunction "P1.03_B6") (pintype "bidirectional"))
    )
    (net (code "92") (name "unconnected-(U2-P1.04-PadC6)") (class "Default")
      (node (ref "U2") (pin "C6") (pinfunction "P1.04_C6") (pintype "bidirectional"))
    )
    (net (code "93") (name "unconnected-(U2-P1.05-PadD6)") (class "Default")
      (node (ref "U2") (pin "D6") (pinfunction "P1.05_D6") (pintype "bidirectional"))
    )
    (net (code "94") (name "unconnected-(U2-P1.06-PadZ6)") (class "Default")
      (node (ref "U2") (pin "Z6") (pinfunction "P1.06_Z6") (pintype "bidirectional"))
    )
    (net (code "95") (name "unconnected-(U2-P1.07-PadE0)") (class "Default")
      (node (ref "U2") (pin "E0") (pinfunction "P1.07_E0") (pintype "bidirectional"))
    )
    (net (code "96") (name "unconnected-(U2-P1.08-PadA6)") (class "Default")
      (node (ref "U2") (pin "A6") (pinfunction "P1.08_A6") (pintype "bidirectional"))
    )
    (net (code "97") (name "unconnected-(U2-P1.09-PadE3)") (class "Default")
      (node (ref "U2") (pin "E3") (pinfunction "P1.09_E3") (pintype "bidirectional"))
    )
    (net (code "98") (name "unconnected-(U2-P1.10-PadZ5)") (class "Default")
      (node (ref "U2") (pin "Z5") (pinfunction "P1.10_Z5") (pintype "bidirectional"))
    )
    (net (code "99") (name "unconnected-(U2-P1.11-PadZ0)") (class "Default")
      (node (ref "U2") (pin "Z0") (pinfunction "P1.11_Z0") (pintype "bidirectional"))
    )
    (net (code "100") (name "unconnected-(U2-P1.12-PadZ1)") (class "Default")
      (node (ref "U2") (pin "Z1") (pinfunction "P1.12_Z1") (pintype "bidirectional"))
    )
    (net (code "101") (name "unconnected-(U2-P1.13-PadZ2)") (class "Default")
      (node (ref "U2") (pin "Z2") (pinfunction "P1.13_Z2") (pintype "bidirectional"))
    )
    (net (code "102") (name "unconnected-(U2-P1.14-PadZ3)") (class "Default")
      (node (ref "U2") (pin "Z3") (pinfunction "P1.14_Z3") (pintype "bidirectional"))
    )
    (net (code "103") (name "unconnected-(U2-P1.15-PadZ4)") (class "Default")
      (node (ref "U2") (pin "Z4") (pinfunction "P1.15_Z4") (pintype "bidirectional"))
    )
    (net (code "104") (name "unconnected-(U2-VBUS-PadF6)") (class "Default")
      (node (ref "U2") (pin "F6") (pinfunction "VBUS_F6") (pintype "power_in"))
    )
    (net (code "105") (name "unconnected-(U3-CTS-Pad15)") (class "Default")
      (node (ref "U3") (pin "15") (pinfunction "CTS_15") (pintype "bidirectional"))
    )
    (net (code "106") (name "unconnected-(U3-GPIO0{slash}CLK-Pad2)") (class "Default")
      (node (ref "U3") (pin "2") (pinfunction "GPIO0/CLK_2") (pintype "bidirectional"))
    )
    (net (code "107") (name "unconnected-(U3-GPIO1{slash}485-Pad1)") (class "Default")
      (node (ref "U3") (pin "1") (pinfunction "GPIO1/485_1") (pintype "bidirectional"))
    )
    (net (code "108") (name "unconnected-(U3-GPIO2{slash}TXT-Pad20)") (class "Default")
      (node (ref "U3") (pin "20") (pinfunction "GPIO2/TXT_20") (pintype "bidirectional"))
    )
    (net (code "109") (name "unconnected-(U3-GPIO3{slash}RXT-Pad19)") (class "Default")
      (node (ref "U3") (pin "19") (pinfunction "GPIO3/RXT_19") (pintype "bidirectional"))
    )
    (net (code "110") (name "unconnected-(U3-RTS-Pad16)") (class "Default")
      (node (ref "U3") (pin "16") (pinfunction "RTS_16") (pintype "bidirectional"))
    )
    (net (code "111") (name "unconnected-(U3-SUSPEND-Pad14)") (class "Default")
      (node (ref "U3") (pin "14") (pinfunction "SUSPEND_14") (pintype "bidirectional"))
    )
    (net (code "112") (name "unconnected-(U3-WAKEUP-Pad13)") (class "Default")
      (node (ref "U3") (pin "13") (pinfunction "WAKEUP_13") (pintype "bidirectional"))
    )
    (net (code "113") (name "unconnected-(U3-~{SUSPEND}-Pad11)") (class "Default")
      (node (ref "U3") (pin "11") (pinfunction "~{SUSPEND}_11") (pintype "bidirectional"))
    )
    (net (code "114") (name "unconnected-(U5-IO33-Pad9)") (class "Default")
      (node (ref "U5") (pin "9") (pinfunction "IO33_9") (pintype "bidirectional"))
    )
    (net (code "115") (name "unconnected-(U5-SENSOR_VN-Pad5)") (class "Default")
      (node (ref "U5") (pin "5") (pinfunction "SENSOR_VN_5") (pintype "bidirectional"))
    )
    (net (code "116") (name "unconnected-(U5-SENSOR_VP-Pad4)") (class "Default")
      (node (ref "U5") (pin "4") (pinfunction "SENSOR_VP_4") (pintype "bidirectional"))
    )
    (net (code "117") (name "unconnected-(U6-IO33-Pad9)") (class "Default")
      (node (ref "U6") (pin "9") (pinfunction "IO33_9") (pintype "bidirectional"))
    )
    (net (code "118") (name "unconnected-(U6-SENSOR_VN-Pad5)") (class "Default")
      (node (ref "U6") (pin "5") (pinfunction "SENSOR_VN_5") (pintype "bidirectional"))
    )
    (net (code "119") (name "unconnected-(U6-SENSOR_VP-Pad4)") (class "Default")
      (node (ref "U6") (pin "4") (pinfunction "SENSOR_VP_4") (pintype "bidirectional"))
    )
    (net (code "120") (name "~{NRF_RESET}") (class "Default")
      (node (ref "J2") (pin "3") (pinfunction "~{RESET}_3") (pintype "bidirectional"))
      (node (ref "U2") (pin "14") (pinfunction "P0.18/RESET_14") (pintype "bidirectional"))
      (node (ref "U5") (pin "36") (pinfunction "IO22_36") (pintype "bidirectional"))
      (node (ref "U6") (pin "36") (pinfunction "IO22_36") (pintype "bidirectional"))
    )
    (net (code "121") (name "~{SD_INSERTED}") (class "Default")
      (node (ref "D1") (pin "P$1") (pinfunction "CATHODE_P$1") (pintype "bidirectional"))
      (node (ref "J1") (pin "SWITCH") (pinfunction "B_SWITCH") (pintype "bidirectional"))
      (node (ref "R13") (pin "2") (pinfunction "2_2") (pintype "passive"))
      (node (ref "U5") (pin "12") (pinfunction "IO27_12") (pintype "bidirectional"))
      (node (ref "U6") (pin "12") (pinfunction "IO27_12") (pintype "bidirectional"))
    )
  )
)
